# Battery_3_7v_Shematic.net
KiCad netlist of a schematic drawn in Altium Designer
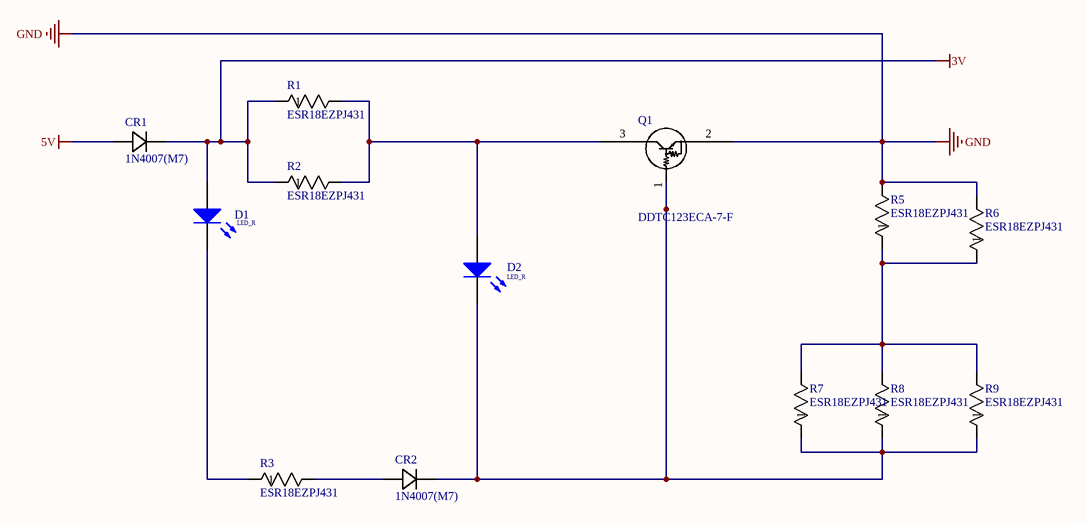
[diagram p0: Battery 3.7v Shematic.SchDoc]

(export (version "E")
  (design (tool "Eeschema 10.0.6"))
  (components
    (comp (ref "CR1")
      (value "1N4007(M7)")
      (footprint "CR_1N4007(M7)_YTS")
      (description "No Description Available")
      (fields (field (name "COPYRIGHT") "Copyright (C) 2022 Ultra Librarian. All rights reserved."))
      (libsource (lib "1N4007_M7_") (part "1N4007(M7)"))
    )
    (comp (ref "CR2")
      (value "1N4007(M7)")
      (footprint "CR_1N4007(M7)_YTS")
      (description "No Description Available")
      (fields (field (name "COPYRIGHT") "Copyright (C) 2022 Ultra Librarian. All rights reserved."))
      (libsource (lib "1N4007_M7_") (part "1N4007(M7)"))
    )
    (comp (ref "D1")
      (value "LED_R")
      (footprint "C1206")
      (description "Typical INFRARED GaAs LED")
      (fields (field (name "PUBLISHER") "Altium Limited"))
      (libsource (lib "Composants_Projet_Sheet_Full") (part "LED0"))
    )
    (comp (ref "D2")
      (value "LED_R")
      (footprint "C1206")
      (description "Typical INFRARED GaAs LED")
      (fields (field (name "PUBLISHER") "Altium Limited"))
      (libsource (lib "Composants_Projet_Sheet_Full") (part "LED0"))
    )
    (comp (ref "Q1")
      (value "DDTC123ECA-7-F")
      (footprint "SOT23_DIO")
      (description "No Description Available")
      (fields (field (name "COPYRIGHT") "Copyright (C) 2022 Ultra Librarian. All rights reserved."))
      (libsource (lib "DDTC123ECA-7-F") (part "DDTC123ECA-7-F"))
    )
    (comp (ref "R1")
      (value "ESR18EZPJ431")
      (footprint "RES_R1206_ROM")
      (description "No Description Available")
      (fields (field (name "COPYRIGHT") "Copyright (C) 2022 Ultra Librarian. All rights reserved."))
      (libsource (lib "ESR18EZPJ431") (part "ESR18EZPJ431"))
    )
    (comp (ref "R2")
      (value "ESR18EZPJ431")
      (footprint "RES_R1206_ROM")
      (description "No Description Available")
      (fields (field (name "COPYRIGHT") "Copyright (C) 2022 Ultra Librarian. All rights reserved."))
      (libsource (lib "ESR18EZPJ431") (part "ESR18EZPJ431"))
    )
    (comp (ref "R3")
      (value "ESR18EZPJ431")
      (footprint "RES_R1206_ROM")
      (description "No Description Available")
      (fields (field (name "COPYRIGHT") "Copyright (C) 2022 Ultra Librarian. All rights reserved."))
      (libsource (lib "ESR18EZPJ431") (part "ESR18EZPJ431"))
    )
    (comp (ref "R5")
      (value "ESR18EZPJ431")
      (footprint "RES_R1206_ROM")
      (description "No Description Available")
      (fields (field (name "COPYRIGHT") "Copyright (C) 2022 Ultra Librarian. All rights reserved."))
      (libsource (lib "ESR18EZPJ431") (part "ESR18EZPJ431"))
    )
    (comp (ref "R6")
      (value "ESR18EZPJ431")
      (footprint "RES_R1206_ROM")
      (description "No Description Available")
      (fields (field (name "COPYRIGHT") "Copyright (C) 2022 Ultra Librarian. All rights reserved."))
      (libsource (lib "ESR18EZPJ431") (part "ESR18EZPJ431"))
    )
    (comp (ref "R7")
      (value "ESR18EZPJ431")
      (footprint "RES_R1206_ROM")
      (description "No Description Available")
      (fields (field (name "COPYRIGHT") "Copyright (C) 2022 Ultra Librarian. All rights reserved."))
      (libsource (lib "ESR18EZPJ431") (part "ESR18EZPJ431"))
    )
    (comp (ref "R8")
      (value "ESR18EZPJ431")
      (footprint "RES_R1206_ROM")
      (description "No Description Available")
      (fields (field (name "COPYRIGHT") "Copyright (C) 2022 Ultra Librarian. All rights reserved."))
      (libsource (lib "ESR18EZPJ431") (part "ESR18EZPJ431"))
    )
    (comp (ref "R9")
      (value "ESR18EZPJ431")
      (footprint "RES_R1206_ROM")
      (description "No Description Available")
      (fields (field (name "COPYRIGHT") "Copyright (C) 2022 Ultra Librarian. All rights reserved."))
      (libsource (lib "ESR18EZPJ431") (part "ESR18EZPJ431"))
    )
  )
  (nets
    (net (code "1") (name "3V") (class "Default")
      (node (ref "CR1") (pin "1") (pinfunction "1_1") (pintype "passive"))
      (node (ref "D1") (pin "1") (pinfunction "A_1") (pintype "passive"))
      (node (ref "R1") (pin "1") (pinfunction "1_1") (pintype "passive"))
      (node (ref "R2") (pin "1") (pinfunction "1_1") (pintype "passive"))
    )
    (net (code "2") (name "5V") (class "Default")
      (node (ref "CR1") (pin "2") (pinfunction "2_2") (pintype "passive"))
    )
    (net (code "3") (name "GND") (class "Default")
      (node (ref "Q1") (pin "2") (pinfunction "2_2") (pintype "passive"))
      (node (ref "R5") (pin "2") (pinfunction "2_2") (pintype "passive"))
      (node (ref "R6") (pin "2") (pinfunction "2_2") (pintype "passive"))
    )
    (net (code "4") (name "Net-(CR2-Pad2)") (class "Default")
      (node (ref "CR2") (pin "2") (pinfunction "2_2") (pintype "passive"))
      (node (ref "R3") (pin "2") (pinfunction "2_2") (pintype "passive"))
    )
    (net (code "5") (name "Net-(D1-K)") (class "Default")
      (node (ref "D1") (pin "2") (pinfunction "K_2") (pintype "passive"))
      (node (ref "R3") (pin "1") (pinfunction "1_1") (pintype "passive"))
    )
    (net (code "6") (name "Net-(D2-A)") (class "Default")
      (node (ref "D2") (pin "1") (pinfunction "A_1") (pintype "passive"))
      (node (ref "Q1") (pin "3") (pinfunction "3_3") (pintype "passive"))
      (node (ref "R1") (pin "2") (pinfunction "2_2") (pintype "passive"))
      (node (ref "R2") (pin "2") (pinfunction "2_2") (pintype "passive"))
    )
    (net (code "7") (name "Net-(D2-K)") (class "Default")
      (node (ref "CR2") (pin "1") (pinfunction "1_1") (pintype "passive"))
      (node (ref "D2") (pin "2") (pinfunction "K_2") (pintype "passive"))
      (node (ref "Q1") (pin "1") (pinfunction "1_1") (pintype "passive"))
      (node (ref "R7") (pin "1") (pinfunction "1_1") (pintype "passive"))
      (node (ref "R8") (pin "1") (pinfunction "1_1") (pintype "passive"))
      (node (ref "R9") (pin "1") (pinfunction "1_1") (pintype "passive"))
    )
    (net (code "8") (name "Net-(R5-Pad1)") (class "Default")
      (node (ref "R5") (pin "1") (pinfunction "1_1") (pintype "passive"))
      (node (ref "R6") (pin "1") (pinfunction "1_1") (pintype "passive"))
      (node (ref "R7") (pin "2") (pinfunction "2_2") (pintype "passive"))
      (node (ref "R8") (pin "2") (pinfunction "2_2") (pintype "passive"))
      (node (ref "R9") (pin "2") (pinfunction "2_2") (pintype "passive"))
    )
  )
)
